# 6_-MIPI-CSI_GPIOs_and_I2C.net
KiCad netlist of a schematic drawn in Altium Designer
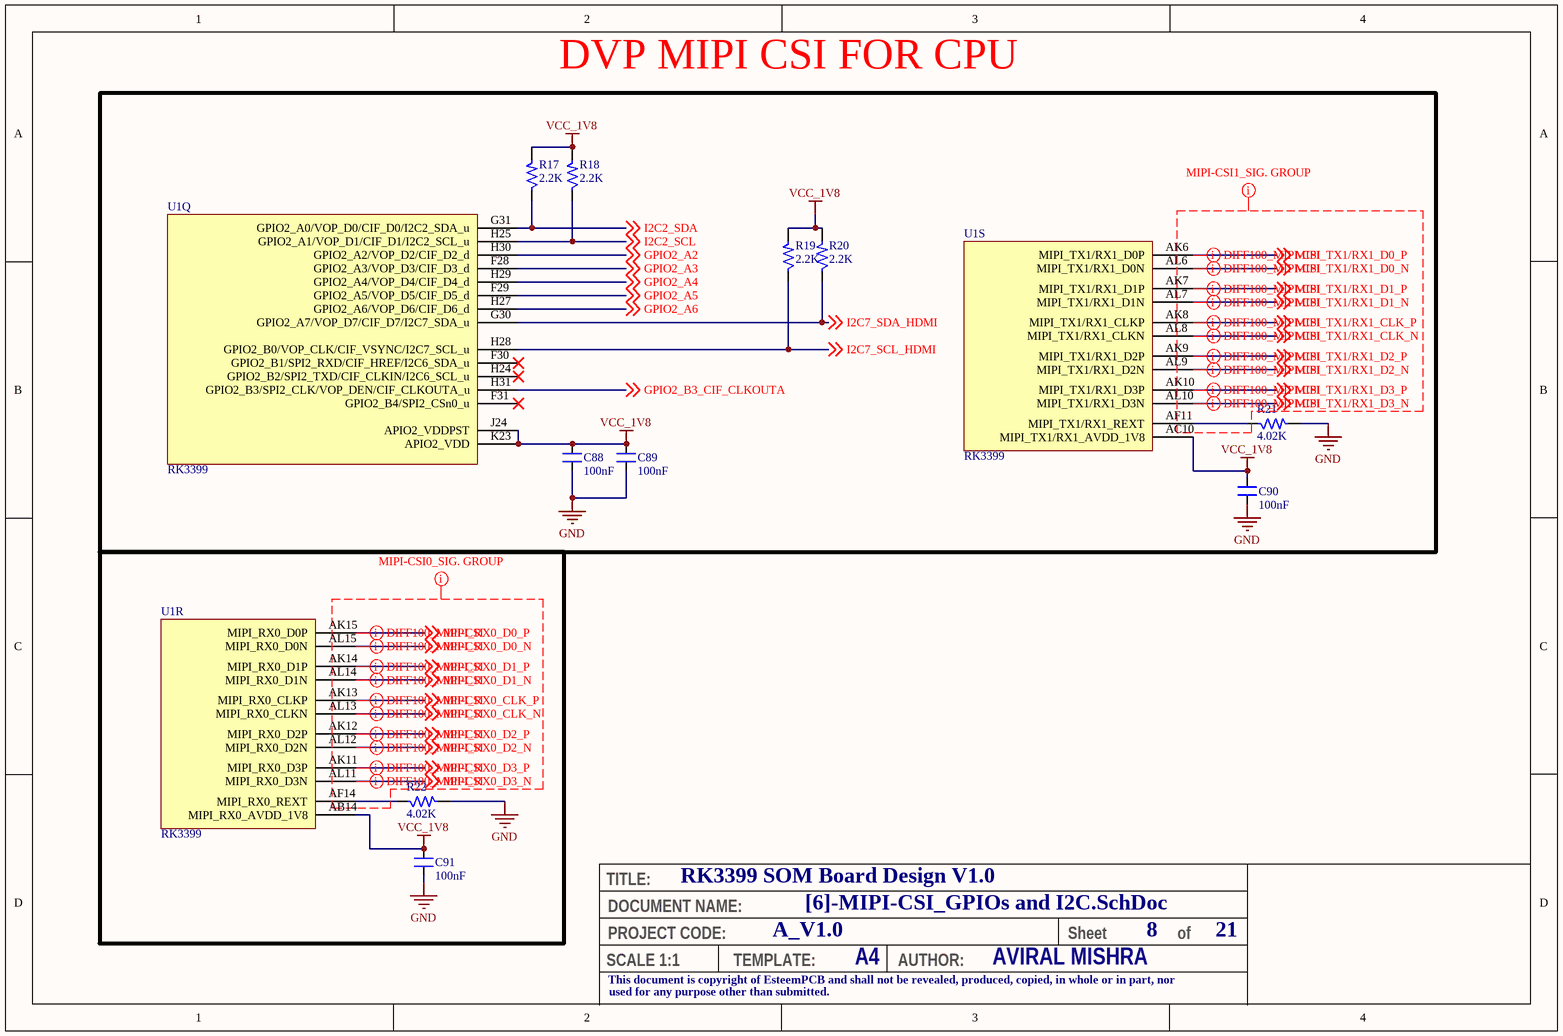
[diagram p0: [6]-MIPI-CSI_GPIOs and I2C.SchDoc]

(export (version "E")
  (design (tool "Eeschema 10.0.6"))
  (components
    (comp (ref "C88")
      (value "100nF")
      (footprint "CAP_0201")
      (description "0.1µF ±10% 25V Ceramic Capacitor X5R 0201 (0603 Metric)")
      (fields
        (field (name "MANUFACTURER") "TDK Corporation")
        (field (name "MANUFACTURER PART NUMBER") "C0603X5R1E104K030BB")
      )
      (libsource (lib "RK3399 _Module_Intlib") (part "CAP_100nF-25V-10%-0201"))
    )
    (comp (ref "C89")
      (value "100nF")
      (footprint "CAP_0201")
      (description "0.1µF ±10% 25V Ceramic Capacitor X5R 0201 (0603 Metric)")
      (fields
        (field (name "MANUFACTURER") "TDK Corporation")
        (field (name "MANUFACTURER PART NUMBER") "C0603X5R1E104K030BB")
      )
      (libsource (lib "RK3399 _Module_Intlib") (part "CAP_100nF-25V-10%-0201"))
    )
    (comp (ref "C90")
      (value "100nF")
      (footprint "CAP_0201")
      (description "0.1µF ±10% 25V Ceramic Capacitor X5R 0201 (0603 Metric)")
      (fields
        (field (name "MANUFACTURER") "TDK Corporation")
        (field (name "MANUFACTURER PART NUMBER") "C0603X5R1E104K030BB")
      )
      (libsource (lib "RK3399 _Module_Intlib") (part "CAP_100nF-25V-10%-0201"))
    )
    (comp (ref "C91")
      (value "100nF")
      (footprint "CAP_0201")
      (description "0.1µF ±10% 25V Ceramic Capacitor X5R 0201 (0603 Metric)")
      (fields
        (field (name "MANUFACTURER") "TDK Corporation")
        (field (name "MANUFACTURER PART NUMBER") "C0603X5R1E104K030BB")
      )
      (libsource (lib "RK3399 _Module_Intlib") (part "CAP_100nF-25V-10%-0201"))
    )
    (comp (ref "R17")
      (value "2.2K")
      (footprint "RES_0201")
      (description "2.2 kOhms ±1% 0.05W, 1/20W Chip Resistor 0201 (0603 Metric) Thick Film")
      (fields
        (field (name "MANUFACTURER") "Stackpole Electronics Inc")
        (field (name "MANUFACTURER PART NUMBER") "RMCF0201FT2K20")
      )
      (libsource (lib "RK3399 _Module_Intlib") (part "RES_2.2K-0.05W-1%-0201"))
    )
    (comp (ref "R18")
      (value "2.2K")
      (footprint "RES_0201")
      (description "2.2 kOhms ±1% 0.05W, 1/20W Chip Resistor 0201 (0603 Metric) Thick Film")
      (fields
        (field (name "MANUFACTURER") "Stackpole Electronics Inc")
        (field (name "MANUFACTURER PART NUMBER") "RMCF0201FT2K20")
      )
      (libsource (lib "RK3399 _Module_Intlib") (part "RES_2.2K-0.05W-1%-0201"))
    )
    (comp (ref "R19")
      (value "2.2K")
      (footprint "RES_0201")
      (description "2.2 kOhms ±1% 0.05W, 1/20W Chip Resistor 0201 (0603 Metric) Thick Film")
      (fields
        (field (name "MANUFACTURER") "Stackpole Electronics Inc")
        (field (name "MANUFACTURER PART NUMBER") "RMCF0201FT2K20")
      )
      (libsource (lib "RK3399 _Module_Intlib") (part "RES_2.2K-0.05W-1%-0201"))
    )
    (comp (ref "R20")
      (value "2.2K")
      (footprint "RES_0201")
      (description "2.2 kOhms ±1% 0.05W, 1/20W Chip Resistor 0201 (0603 Metric) Thick Film")
      (fields
        (field (name "MANUFACTURER") "Stackpole Electronics Inc")
        (field (name "MANUFACTURER PART NUMBER") "RMCF0201FT2K20")
      )
      (libsource (lib "RK3399 _Module_Intlib") (part "RES_2.2K-0.05W-1%-0201"))
    )
    (comp (ref "R21")
      (value "4.02K")
      (footprint "RES_0201")
      (description "4.02 kOhms ±1% 0.05W, 1/20W Chip Resistor 0201 (0603 Metric) Thick Film")
      (fields
        (field (name "MANUFACTURER") "Yageo")
        (field (name "MANUFACTURER PART NUMBER") "RC0201FR-074K02L")
      )
      (libsource (lib "RK3399 _Module_Intlib") (part "RES_4.02K-0.05W-1%-0201"))
    )
    (comp (ref "R22")
      (value "4.02K")
      (footprint "RES_0201")
      (description "4.02 kOhms ±1% 0.05W, 1/20W Chip Resistor 0201 (0603 Metric) Thick Film")
      (fields
        (field (name "MANUFACTURER") "Yageo")
        (field (name "MANUFACTURER PART NUMBER") "RC0201FR-074K02L")
      )
      (libsource (lib "RK3399 _Module_Intlib") (part "RES_4.02K-0.05W-1%-0201"))
    )
    (comp (ref "U1")
      (value "RK3399")
      (footprint "FBGA828_23_826X826")
      (description "RK3399 is a low power, high performance processor for computing, personal mobile.")
      (fields (field (name "MANUFACTURER") "Rockchip"))
      (libsource (lib "RK3399 _Module_Schlib") (part "IC_RK3399-FCBGA828"))
    )
  )
  (nets
    (net (code "1") (name "GND") (class "Default")
      (node (ref "C88") (pin "1") (pinfunction "1_1") (pintype "passive"))
      (node (ref "C89") (pin "1") (pinfunction "1_1") (pintype "passive"))
      (node (ref "C90") (pin "1") (pinfunction "1_1") (pintype "passive"))
      (node (ref "C91") (pin "1") (pinfunction "1_1") (pintype "passive"))
      (node (ref "R21") (pin "2") (pinfunction "2_2") (pintype "passive"))
      (node (ref "R22") (pin "2") (pinfunction "2_2") (pintype "passive"))
    )
    (net (code "2") (name "GPIO2_A2") (class "Default")
      (node (ref "U1") (pin "H30") (pinfunction "GPIO2_A2/VOP_D2/CIF_D2_d_H30") (pintype "passive"))
    )
    (net (code "3") (name "GPIO2_A3") (class "Default")
      (node (ref "U1") (pin "F28") (pinfunction "GPIO2_A3/VOP_D3/CIF_D3_d_F28") (pintype "passive"))
    )
    (net (code "4") (name "GPIO2_A4") (class "Default")
      (node (ref "U1") (pin "H29") (pinfunction "GPIO2_A4/VOP_D4/CIF_D4_d_H29") (pintype "passive"))
    )
    (net (code "5") (name "GPIO2_A5") (class "Default")
      (node (ref "U1") (pin "F29") (pinfunction "GPIO2_A5/VOP_D5/CIF_D5_d_F29") (pintype "passive"))
    )
    (net (code "6") (name "GPIO2_A6") (class "Default")
      (node (ref "U1") (pin "H27") (pinfunction "GPIO2_A6/VOP_D6/CIF_D6_d_H27") (pintype "passive"))
    )
    (net (code "7") (name "GPIO2_B3_CIF_CLKOUTA") (class "Default")
      (node (ref "U1") (pin "H31") (pinfunction "GPIO2_B3/SPI2_CLK/VOP_DEN/CIF_CLKOUTA_u_H31") (pintype "passive"))
    )
    (net (code "8") (name "I2C2_SCL") (class "Default")
      (node (ref "R18") (pin "1") (pinfunction "1_1") (pintype "passive"))
      (node (ref "U1") (pin "H25") (pinfunction "GPIO2_A1/VOP_D1/CIF_D1/I2C2_SCL_u_H25") (pintype "passive"))
    )
    (net (code "9") (name "I2C2_SDA") (class "Default")
      (node (ref "R17") (pin "1") (pinfunction "1_1") (pintype "passive"))
      (node (ref "U1") (pin "G31") (pinfunction "GPIO2_A0/VOP_D0/CIF_D0/I2C2_SDA_u_G31") (pintype "passive"))
    )
    (net (code "10") (name "I2C7_SCL_HDMI") (class "Default")
      (node (ref "R19") (pin "1") (pinfunction "1_1") (pintype "passive"))
      (node (ref "U1") (pin "H28") (pinfunction "GPIO2_B0/VOP_CLK/CIF_VSYNC/I2C7_SCL_u_H28") (pintype "passive"))
    )
    (net (code "11") (name "I2C7_SDA_HDMI") (class "Default")
      (node (ref "R20") (pin "1") (pinfunction "1_1") (pintype "passive"))
      (node (ref "U1") (pin "G30") (pinfunction "GPIO2_A7/VOP_D7/CIF_D7/I2C7_SDA_u_G30") (pintype "passive"))
    )
    (net (code "12") (name "MIPI_RX0_CLK_N") (class "Default")
      (node (ref "U1") (pin "AL13") (pinfunction "MIPI_RX0_CLKN_AL13") (pintype "passive"))
    )
    (net (code "13") (name "MIPI_RX0_CLK_P") (class "Default")
      (node (ref "U1") (pin "AK13") (pinfunction "MIPI_RX0_CLKP_AK13") (pintype "passive"))
    )
    (net (code "14") (name "MIPI_RX0_D0_N") (class "Default")
      (node (ref "U1") (pin "AL15") (pinfunction "MIPI_RX0_D0N_AL15") (pintype "passive"))
    )
    (net (code "15") (name "MIPI_RX0_D0_P") (class "Default")
      (node (ref "U1") (pin "AK15") (pinfunction "MIPI_RX0_D0P_AK15") (pintype "passive"))
    )
    (net (code "16") (name "MIPI_RX0_D1_N") (class "Default")
      (node (ref "U1") (pin "AL14") (pinfunction "MIPI_RX0_D1N_AL14") (pintype "passive"))
    )
    (net (code "17") (name "MIPI_RX0_D1_P") (class "Default")
      (node (ref "U1") (pin "AK14") (pinfunction "MIPI_RX0_D1P_AK14") (pintype "passive"))
    )
    (net (code "18") (name "MIPI_RX0_D2_N") (class "Default")
      (node (ref "U1") (pin "AL12") (pinfunction "MIPI_RX0_D2N_AL12") (pintype "passive"))
    )
    (net (code "19") (name "MIPI_RX0_D2_P") (class "Default")
      (node (ref "U1") (pin "AK12") (pinfunction "MIPI_RX0_D2P_AK12") (pintype "passive"))
    )
    (net (code "20") (name "MIPI_RX0_D3_N") (class "Default")
      (node (ref "U1") (pin "AL11") (pinfunction "MIPI_RX0_D3N_AL11") (pintype "passive"))
    )
    (net (code "21") (name "MIPI_RX0_D3_P") (class "Default")
      (node (ref "U1") (pin "AK11") (pinfunction "MIPI_RX0_D3P_AK11") (pintype "passive"))
    )
    (net (code "22") (name "MIPI_TX1{slash}RX1_CLK_N") (class "Default")
      (node (ref "U1") (pin "AL8") (pinfunction "MIPI_TX1/RX1_CLKN_AL8") (pintype "passive"))
    )
    (net (code "23") (name "MIPI_TX1{slash}RX1_CLK_P") (class "Default")
      (node (ref "U1") (pin "AK8") (pinfunction "MIPI_TX1/RX1_CLKP_AK8") (pintype "passive"))
    )
    (net (code "24") (name "MIPI_TX1{slash}RX1_D0_N") (class "Default")
      (node (ref "U1") (pin "AL6") (pinfunction "MIPI_TX1/RX1_D0N_AL6") (pintype "passive"))
    )
    (net (code "25") (name "MIPI_TX1{slash}RX1_D0_P") (class "Default")
      (node (ref "U1") (pin "AK6") (pinfunction "MIPI_TX1/RX1_D0P_AK6") (pintype "passive"))
    )
    (net (code "26") (name "MIPI_TX1{slash}RX1_D1_N") (class "Default")
      (node (ref "U1") (pin "AL7") (pinfunction "MIPI_TX1/RX1_D1N_AL7") (pintype "passive"))
    )
    (net (code "27") (name "MIPI_TX1{slash}RX1_D1_P") (class "Default")
      (node (ref "U1") (pin "AK7") (pinfunction "MIPI_TX1/RX1_D1P_AK7") (pintype "passive"))
    )
    (net (code "28") (name "MIPI_TX1{slash}RX1_D2_N") (class "Default")
      (node (ref "U1") (pin "AL9") (pinfunction "MIPI_TX1/RX1_D2N_AL9") (pintype "passive"))
    )
    (net (code "29") (name "MIPI_TX1{slash}RX1_D2_P") (class "Default")
      (node (ref "U1") (pin "AK9") (pinfunction "MIPI_TX1/RX1_D2P_AK9") (pintype "passive"))
    )
    (net (code "30") (name "MIPI_TX1{slash}RX1_D3_N") (class "Default")
      (node (ref "U1") (pin "AL10") (pinfunction "MIPI_TX1/RX1_D3N_AL10") (pintype "passive"))
    )
    (net (code "31") (name "MIPI_TX1{slash}RX1_D3_P") (class "Default")
      (node (ref "U1") (pin "AK10") (pinfunction "MIPI_TX1/RX1_D3P_AK10") (pintype "passive"))
    )
    (net (code "32") (name "Net-(U1R-MIPI_RX0_REXT)") (class "Default")
      (node (ref "R22") (pin "1") (pinfunction "1_1") (pintype "passive"))
      (node (ref "U1") (pin "AF14") (pinfunction "MIPI_RX0_REXT_AF14") (pintype "passive"))
    )
    (net (code "33") (name "Net-(U1S-MIPI_TX1{slash}RX1_REXT)") (class "Default")
      (node (ref "R21") (pin "1") (pinfunction "1_1") (pintype "passive"))
      (node (ref "U1") (pin "AF11") (pinfunction "MIPI_TX1/RX1_REXT_AF11") (pintype "passive"))
    )
    (net (code "34") (name "VCC_1V8") (class "Default")
      (node (ref "C88") (pin "2") (pinfunction "2_2") (pintype "passive"))
      (node (ref "C89") (pin "2") (pinfunction "2_2") (pintype "passive"))
      (node (ref "C90") (pin "2") (pinfunction "2_2") (pintype "passive"))
      (node (ref "C91") (pin "2") (pinfunction "2_2") (pintype "passive"))
      (node (ref "R17") (pin "2") (pinfunction "2_2") (pintype "passive"))
      (node (ref "R18") (pin "2") (pinfunction "2_2") (pintype "passive"))
      (node (ref "R19") (pin "2") (pinfunction "2_2") (pintype "passive"))
      (node (ref "R20") (pin "2") (pinfunction "2_2") (pintype "passive"))
      (node (ref "U1") (pin "AB14") (pinfunction "MIPI_RX0_AVDD_1V8_AB14") (pintype "passive"))
      (node (ref "U1") (pin "AC10") (pinfunction "MIPI_TX1/RX1_AVDD_1V8_AC10") (pintype "passive"))
      (node (ref "U1") (pin "J24") (pinfunction "APIO2_VDDPST_J24") (pintype "passive"))
      (node (ref "U1") (pin "K23") (pinfunction "APIO2_VDD_K23") (pintype "passive"))
    )
    (net (code "35") (name "unconnected-(U1Q-GPIO2_B1{slash}SPI2_RXD{slash}CIF_HREF{slash}I2C6_SDA_u-PadF30)") (class "Default")
      (node (ref "U1") (pin "F30") (pinfunction "GPIO2_B1/SPI2_RXD/CIF_HREF/I2C6_SDA_u_F30") (pintype "passive+no_connect"))
    )
    (net (code "36") (name "unconnected-(U1Q-GPIO2_B2{slash}SPI2_TXD{slash}CIF_CLKIN{slash}I2C6_SCL_u-PadH24)") (class "Default")
      (node (ref "U1") (pin "H24") (pinfunction "GPIO2_B2/SPI2_TXD/CIF_CLKIN/I2C6_SCL_u_H24") (pintype "passive+no_connect"))
    )
    (net (code "37") (name "unconnected-(U1Q-GPIO2_B4{slash}SPI2_CSn0_u-PadF31)") (class "Default")
      (node (ref "U1") (pin "F31") (pinfunction "GPIO2_B4/SPI2_CSn0_u_F31") (pintype "passive+no_connect"))
    )
  )
)
